# CPU.net
KiCad netlist of a schematic drawn in Altium Designer
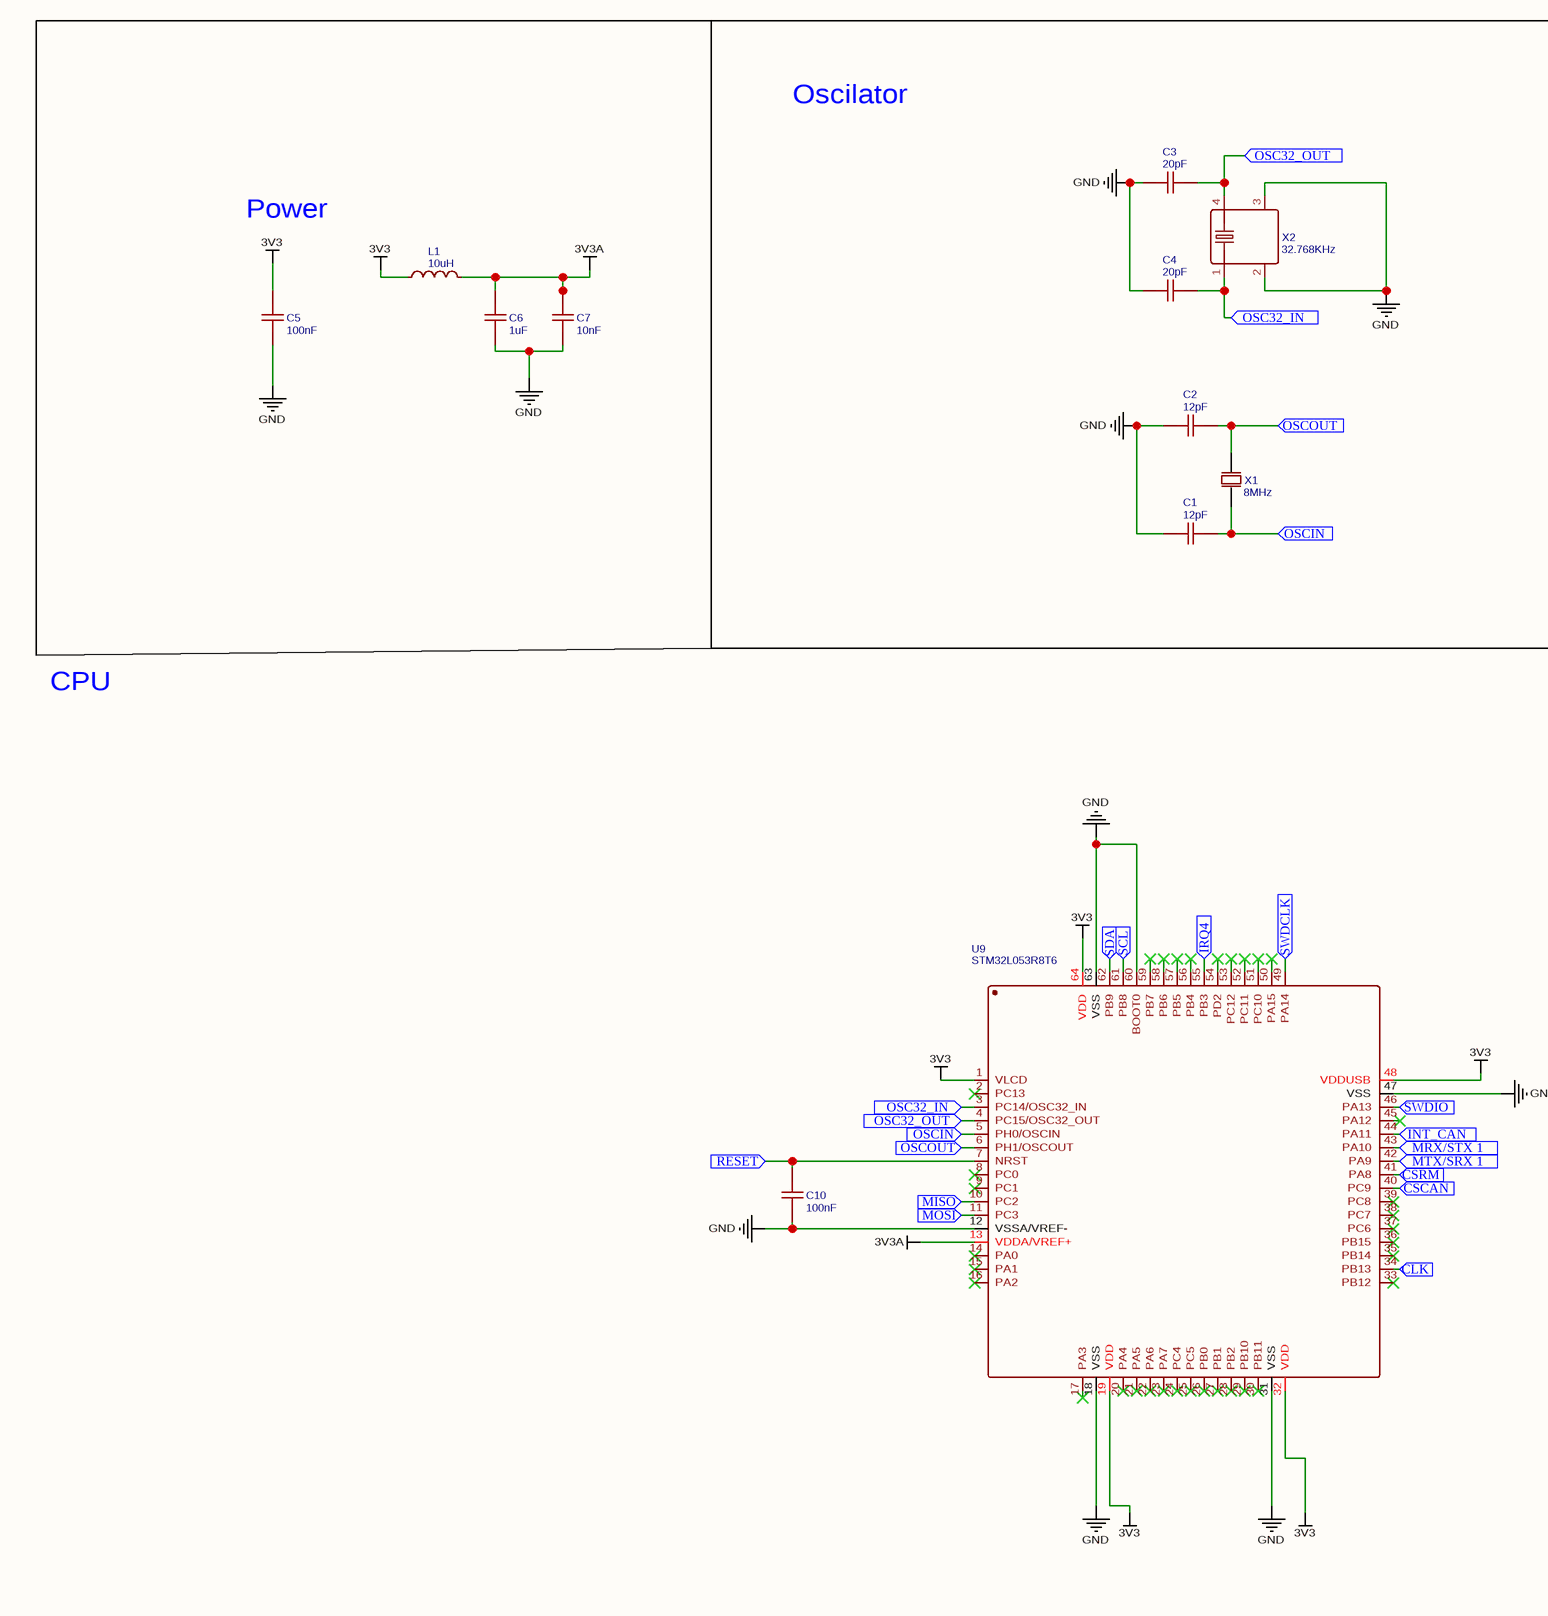
[diagram p0: CPU.schdoc, left]
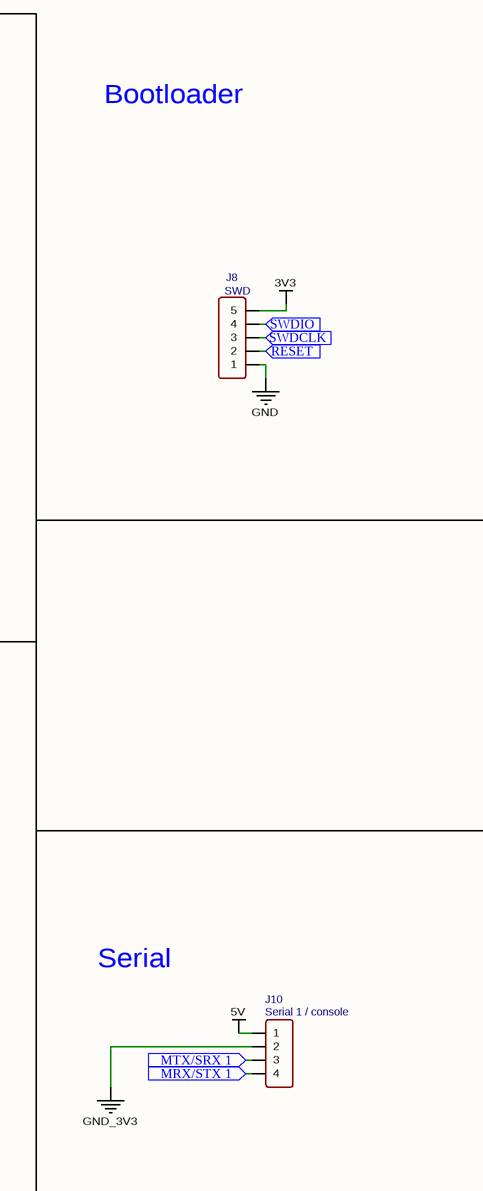
[diagram p1: CPU.schdoc, right]

(export (version "E")
  (design (tool "Eeschema 10.0.6"))
  (components
    (comp (ref "C1")
      (value "12pF")
      (fields
        (field (name "BOM_SUPPLIER PART") "C170110")
        (field (name "BOM_MANUFACTURER PART") "CL21C120JBANNNC")
        (field (name "CONTRIBUTOR") "LCEDA_Lib")
      )
      (libsource (lib "altium-import") (part "root_0_12pF_"))
    )
    (comp (ref "C2")
      (value "12pF")
      (fields
        (field (name "BOM_SUPPLIER PART") "C170110")
        (field (name "BOM_MANUFACTURER PART") "CL21C120JBANNNC")
        (field (name "CONTRIBUTOR") "LCEDA_Lib")
      )
      (libsource (lib "altium-import") (part "root_0_12pF_"))
    )
    (comp (ref "C3")
      (value "20pF")
      (fields
        (field (name "BOM_SUPPLIER PART") "C105173")
        (field (name "BOM_MANUFACTURER PART") "CC0805JRNPO9BN200")
        (field (name "CONTRIBUTOR") "LCEDA_Lib")
      )
      (libsource (lib "altium-import") (part "root_0_20pF_"))
    )
    (comp (ref "C4")
      (value "20pF")
      (fields
        (field (name "BOM_SUPPLIER PART") "C105173")
        (field (name "BOM_MANUFACTURER PART") "CC0805JRNPO9BN200")
        (field (name "CONTRIBUTOR") "LCEDA_Lib")
      )
      (libsource (lib "altium-import") (part "root_0_20pF_"))
    )
    (comp (ref "C5")
      (value "100nF")
      (fields
        (field (name "BOM_SUPPLIER PART") "C49678")
        (field (name "BOM_MANUFACTURER PART") "CC0805KRX7R9BB104")
        (field (name "CONTRIBUTOR") "LCEDA_Lib")
      )
      (libsource (lib "altium-import") (part "root_1_100nF_"))
    )
    (comp (ref "C6")
      (value "1uF")
      (fields
        (field (name "BOM_SUPPLIER PART") "C77080")
        (field (name "BOM_MANUFACTURER PART") "GRM21BR71E105KA99L")
        (field (name "CONTRIBUTOR") "LCEDA_Lib")
      )
      (libsource (lib "altium-import") (part "root_1_1uF_"))
    )
    (comp (ref "C7")
      (value "10nF")
      (fields
        (field (name "BOM_SUPPLIER PART") "C2971995")
        (field (name "BOM_MANUFACTURER PART") "0805CG103J500NT")
        (field (name "CONTRIBUTOR") "LCEDA_Lib")
      )
      (libsource (lib "altium-import") (part "root_1_10nF_"))
    )
    (comp (ref "C10")
      (value "100nF")
      (fields
        (field (name "BOM_SUPPLIER PART") "C49678")
        (field (name "BOM_MANUFACTURER PART") "CC0805KRX7R9BB104")
        (field (name "CONTRIBUTOR") "LCEDA_Lib")
      )
      (libsource (lib "altium-import") (part "root_1_100nF_"))
    )
    (comp (ref "J8")
      (value "SWD")
      (fields (field (name "BOM_SUPPLIER PART") "C358687") (field (name "CONTRIBUTOR") "LCEDA_Lib"))
      (libsource (lib "altium-import") (part "root_2_SWD_"))
    )
    (comp (ref "J10")
      (value "Serial 1 / console")
      (fields (field (name "BOM_SUPPLIER PART") "C124378") (field (name "CONTRIBUTOR") "LCEDA_Lib"))
      (libsource (lib "altium-import") (part "root_0_Serial 1 / console_"))
    )
    (comp (ref "L1")
      (value "10uH")
      (fields
        (field (name "BOM_MANUFACTURER PART") "CMI321609X100KT")
        (field (name "BOM_SUPPLIER PART") "C1051")
      )
      (libsource (lib "altium-import") (part "root_0_10uH_"))
    )
    (comp (ref "U9")
      (value "STM32L053R8T6")
      (fields
        (field (name "BOM_MANUFACTURER PART") "STM32L053R6T6")
        (field (name "BOM_SUPPLIER PART") "C1339433")
      )
      (libsource (lib "altium-import") (part "root_0_STM32L053R8T6_"))
    )
    (comp (ref "X1")
      (value "8MHz")
      (fields
        (field (name "BOM_MANUFACTURER PART") "X50328MSB2GI")
        (field (name "BOM_SUPPLIER PART") "C115962")
      )
      (libsource (lib "altium-import") (part "root_1_8MHz_"))
    )
    (comp (ref "X2")
      (value "32.768KHz")
      (fields
        (field (name "BOM_MANUFACTURER PART") "MC-306 32.768kHz 6.0pF 20ppm")
        (field (name "BOM_SUPPLIER PART") "C83979")
        (field (name "CONTRIBUTOR") "LCSC")
      )
      (libsource (lib "altium-import") (part "root_0_32.768KHz_"))
    )
  )
  (nets
    (net (code "1") (name "/CLK") (class "Default")
      (node (ref "U9") (pin "34") (pinfunction "PB13_34") (pintype "passive"))
    )
    (net (code "2") (name "/CSCAN") (class "Default")
      (node (ref "U9") (pin "40") (pinfunction "PC9_40") (pintype "passive"))
    )
    (net (code "3") (name "/CSRM") (class "Default")
      (node (ref "U9") (pin "41") (pinfunction "PA8_41") (pintype "passive"))
    )
    (net (code "4") (name "/INT_CAN") (class "Default")
      (node (ref "U9") (pin "44") (pinfunction "PA11_44") (pintype "passive"))
    )
    (net (code "5") (name "/IRQ4") (class "Default")
      (node (ref "U9") (pin "55") (pinfunction "PB3_55") (pintype "passive"))
    )
    (net (code "6") (name "/MISO") (class "Default")
      (node (ref "U9") (pin "10") (pinfunction "PC2_10") (pintype "passive"))
    )
    (net (code "7") (name "/MOSI") (class "Default")
      (node (ref "U9") (pin "11") (pinfunction "PC3_11") (pintype "passive"))
    )
    (net (code "8") (name "/MRX{slash}STX 1") (class "Default")
      (node (ref "J10") (pin "4") (pinfunction "4_4") (pintype "passive"))
      (node (ref "U9") (pin "43") (pinfunction "PA10_43") (pintype "passive"))
    )
    (net (code "9") (name "/MTX{slash}SRX 1") (class "Default")
      (node (ref "J10") (pin "3") (pinfunction "3_3") (pintype "passive"))
      (node (ref "U9") (pin "42") (pinfunction "PA9_42") (pintype "passive"))
    )
    (net (code "10") (name "/OSC32_IN") (class "Default")
      (node (ref "C4") (pin "2") (pinfunction "2_2") (pintype "passive"))
      (node (ref "U9") (pin "3") (pinfunction "PC14/OSC32_IN_3") (pintype "passive"))
      (node (ref "X2") (pin "1") (pinfunction "1_1") (pintype "passive"))
    )
    (net (code "11") (name "/OSC32_OUT") (class "Default")
      (node (ref "C3") (pin "2") (pinfunction "2_2") (pintype "passive"))
      (node (ref "U9") (pin "4") (pinfunction "PC15/OSC32_OUT_4") (pintype "passive"))
      (node (ref "X2") (pin "4") (pinfunction "4_4") (pintype "passive"))
    )
    (net (code "12") (name "/OSCIN") (class "Default")
      (node (ref "C1") (pin "2") (pinfunction "2_2") (pintype "passive"))
      (node (ref "U9") (pin "5") (pinfunction "PH0/OSCIN_5") (pintype "passive"))
      (node (ref "X1") (pin "1") (pinfunction "OSC1_1") (pintype "passive"))
    )
    (net (code "13") (name "/OSCOUT") (class "Default")
      (node (ref "C2") (pin "2") (pinfunction "2_2") (pintype "passive"))
      (node (ref "U9") (pin "6") (pinfunction "PH1/OSCOUT_6") (pintype "passive"))
      (node (ref "X1") (pin "2") (pinfunction "OSC2_2") (pintype "passive"))
    )
    (net (code "14") (name "/RESET") (class "Default")
      (node (ref "C10") (pin "2") (pinfunction "2_2") (pintype "passive"))
      (node (ref "J8") (pin "2") (pinfunction "2_2") (pintype "passive"))
      (node (ref "U9") (pin "7") (pinfunction "NRST_7") (pintype "passive"))
    )
    (net (code "15") (name "/SCL") (class "Default")
      (node (ref "U9") (pin "61") (pinfunction "PB8_61") (pintype "passive"))
    )
    (net (code "16") (name "/SDA") (class "Default")
      (node (ref "U9") (pin "62") (pinfunction "PB9_62") (pintype "passive"))
    )
    (net (code "17") (name "/SWDCLK") (class "Default")
      (node (ref "J8") (pin "3") (pinfunction "3_3") (pintype "passive"))
      (node (ref "U9") (pin "49") (pinfunction "PA14_49") (pintype "passive"))
    )
    (net (code "18") (name "/SWDIO") (class "Default")
      (node (ref "J8") (pin "4") (pinfunction "4_4") (pintype "passive"))
      (node (ref "U9") (pin "46") (pinfunction "PA13_46") (pintype "passive"))
    )
    (net (code "19") (name "3V3") (class "Default")
      (node (ref "C5") (pin "2") (pinfunction "2_2") (pintype "passive"))
      (node (ref "J8") (pin "5") (pinfunction "5_5") (pintype "passive"))
      (node (ref "L1") (pin "1") (pinfunction "1_1") (pintype "passive"))
      (node (ref "U9") (pin "1") (pinfunction "VLCD_1") (pintype "passive"))
      (node (ref "U9") (pin "19") (pinfunction "VDD_19") (pintype "passive"))
      (node (ref "U9") (pin "32") (pinfunction "VDD_32") (pintype "passive"))
      (node (ref "U9") (pin "48") (pinfunction "VDDUSB_48") (pintype "passive"))
      (node (ref "U9") (pin "64") (pinfunction "VDD_64") (pintype "passive"))
    )
    (net (code "20") (name "3V3A") (class "Default")
      (node (ref "C6") (pin "2") (pinfunction "2_2") (pintype "passive"))
      (node (ref "C7") (pin "2") (pinfunction "2_2") (pintype "passive"))
      (node (ref "L1") (pin "2") (pinfunction "2_2") (pintype "passive"))
      (node (ref "U9") (pin "13") (pinfunction "VDDA/VREF+_13") (pintype "passive"))
    )
    (net (code "21") (name "5V") (class "Default")
      (node (ref "J10") (pin "1") (pinfunction "1_1") (pintype "passive"))
    )
    (net (code "22") (name "GND") (class "Default")
      (node (ref "C1") (pin "1") (pinfunction "1_1") (pintype "passive"))
      (node (ref "C10") (pin "1") (pinfunction "1_1") (pintype "passive"))
      (node (ref "C2") (pin "1") (pinfunction "1_1") (pintype "passive"))
      (node (ref "C3") (pin "1") (pinfunction "1_1") (pintype "passive"))
      (node (ref "C4") (pin "1") (pinfunction "1_1") (pintype "passive"))
      (node (ref "C5") (pin "1") (pinfunction "1_1") (pintype "passive"))
      (node (ref "C6") (pin "1") (pinfunction "1_1") (pintype "passive"))
      (node (ref "C7") (pin "1") (pinfunction "1_1") (pintype "passive"))
      (node (ref "J8") (pin "1") (pinfunction "1_1") (pintype "passive"))
      (node (ref "U9") (pin "12") (pinfunction "VSSA/VREF-_12") (pintype "passive"))
      (node (ref "U9") (pin "18") (pinfunction "VSS_18") (pintype "passive"))
      (node (ref "U9") (pin "31") (pinfunction "VSS_31") (pintype "passive"))
      (node (ref "U9") (pin "47") (pinfunction "VSS_47") (pintype "passive"))
      (node (ref "U9") (pin "60") (pinfunction "BOOT0_60") (pintype "passive"))
      (node (ref "U9") (pin "63") (pinfunction "VSS_63") (pintype "passive"))
      (node (ref "X2") (pin "2") (pinfunction "2_2") (pintype "passive"))
      (node (ref "X2") (pin "3") (pinfunction "3_3") (pintype "passive"))
    )
    (net (code "23") (name "GND_3V3") (class "Default")
      (node (ref "J10") (pin "2") (pinfunction "2_2") (pintype "passive"))
    )
    (net (code "24") (name "unconnected-(U9-PA0-Pad14)") (class "Default")
      (node (ref "U9") (pin "14") (pinfunction "PA0_14") (pintype "passive+no_connect"))
    )
    (net (code "25") (name "unconnected-(U9-PA1-Pad15)") (class "Default")
      (node (ref "U9") (pin "15") (pinfunction "PA1_15") (pintype "passive+no_connect"))
    )
    (net (code "26") (name "unconnected-(U9-PA2-Pad16)") (class "Default")
      (node (ref "U9") (pin "16") (pinfunction "PA2_16") (pintype "passive+no_connect"))
    )
    (net (code "27") (name "unconnected-(U9-PA3-Pad17)") (class "Default")
      (node (ref "U9") (pin "17") (pinfunction "PA3_17") (pintype "passive+no_connect"))
    )
    (net (code "28") (name "unconnected-(U9-PA4-Pad20)") (class "Default")
      (node (ref "U9") (pin "20") (pinfunction "PA4_20") (pintype "passive+no_connect"))
    )
    (net (code "29") (name "unconnected-(U9-PA5-Pad21)") (class "Default")
      (node (ref "U9") (pin "21") (pinfunction "PA5_21") (pintype "passive+no_connect"))
    )
    (net (code "30") (name "unconnected-(U9-PA6-Pad22)") (class "Default")
      (node (ref "U9") (pin "22") (pinfunction "PA6_22") (pintype "passive+no_connect"))
    )
    (net (code "31") (name "unconnected-(U9-PA7-Pad23)") (class "Default")
      (node (ref "U9") (pin "23") (pinfunction "PA7_23") (pintype "passive+no_connect"))
    )
    (net (code "32") (name "unconnected-(U9-PA12-Pad45)") (class "Default")
      (node (ref "U9") (pin "45") (pinfunction "PA12_45") (pintype "passive+no_connect"))
    )
    (net (code "33") (name "unconnected-(U9-PA15-Pad50)") (class "Default")
      (node (ref "U9") (pin "50") (pinfunction "PA15_50") (pintype "passive+no_connect"))
    )
    (net (code "34") (name "unconnected-(U9-PB0-Pad26)") (class "Default")
      (node (ref "U9") (pin "26") (pinfunction "PB0_26") (pintype "passive+no_connect"))
    )
    (net (code "35") (name "unconnected-(U9-PB1-Pad27)") (class "Default")
      (node (ref "U9") (pin "27") (pinfunction "PB1_27") (pintype "passive+no_connect"))
    )
    (net (code "36") (name "unconnected-(U9-PB2-Pad28)") (class "Default")
      (node (ref "U9") (pin "28") (pinfunction "PB2_28") (pintype "passive+no_connect"))
    )
    (net (code "37") (name "unconnected-(U9-PB4-Pad56)") (class "Default")
      (node (ref "U9") (pin "56") (pinfunction "PB4_56") (pintype "passive+no_connect"))
    )
    (net (code "38") (name "unconnected-(U9-PB5-Pad57)") (class "Default")
      (node (ref "U9") (pin "57") (pinfunction "PB5_57") (pintype "passive+no_connect"))
    )
    (net (code "39") (name "unconnected-(U9-PB6-Pad58)") (class "Default")
      (node (ref "U9") (pin "58") (pinfunction "PB6_58") (pintype "passive+no_connect"))
    )
    (net (code "40") (name "unconnected-(U9-PB7-Pad59)") (class "Default")
      (node (ref "U9") (pin "59") (pinfunction "PB7_59") (pintype "passive+no_connect"))
    )
    (net (code "41") (name "unconnected-(U9-PB10-Pad29)") (class "Default")
      (node (ref "U9") (pin "29") (pinfunction "PB10_29") (pintype "passive+no_connect"))
    )
    (net (code "42") (name "unconnected-(U9-PB11-Pad30)") (class "Default")
      (node (ref "U9") (pin "30") (pinfunction "PB11_30") (pintype "passive+no_connect"))
    )
    (net (code "43") (name "unconnected-(U9-PB12-Pad33)") (class "Default")
      (node (ref "U9") (pin "33") (pinfunction "PB12_33") (pintype "passive+no_connect"))
    )
    (net (code "44") (name "unconnected-(U9-PB14-Pad35)") (class "Default")
      (node (ref "U9") (pin "35") (pinfunction "PB14_35") (pintype "passive+no_connect"))
    )
    (net (code "45") (name "unconnected-(U9-PB15-Pad36)") (class "Default")
      (node (ref "U9") (pin "36") (pinfunction "PB15_36") (pintype "passive+no_connect"))
    )
    (net (code "46") (name "unconnected-(U9-PC0-Pad8)") (class "Default")
      (node (ref "U9") (pin "8") (pinfunction "PC0_8") (pintype "passive+no_connect"))
    )
    (net (code "47") (name "unconnected-(U9-PC1-Pad9)") (class "Default")
      (node (ref "U9") (pin "9") (pinfunction "PC1_9") (pintype "passive+no_connect"))
    )
    (net (code "48") (name "unconnected-(U9-PC4-Pad24)") (class "Default")
      (node (ref "U9") (pin "24") (pinfunction "PC4_24") (pintype "passive+no_connect"))
    )
    (net (code "49") (name "unconnected-(U9-PC5-Pad25)") (class "Default")
      (node (ref "U9") (pin "25") (pinfunction "PC5_25") (pintype "passive+no_connect"))
    )
    (net (code "50") (name "unconnected-(U9-PC6-Pad37)") (class "Default")
      (node (ref "U9") (pin "37") (pinfunction "PC6_37") (pintype "passive+no_connect"))
    )
    (net (code "51") (name "unconnected-(U9-PC7-Pad38)") (class "Default")
      (node (ref "U9") (pin "38") (pinfunction "PC7_38") (pintype "passive+no_connect"))
    )
    (net (code "52") (name "unconnected-(U9-PC8-Pad39)") (class "Default")
      (node (ref "U9") (pin "39") (pinfunction "PC8_39") (pintype "passive+no_connect"))
    )
    (net (code "53") (name "unconnected-(U9-PC10-Pad51)") (class "Default")
      (node (ref "U9") (pin "51") (pinfunction "PC10_51") (pintype "passive+no_connect"))
    )
    (net (code "54") (name "unconnected-(U9-PC11-Pad52)") (class "Default")
      (node (ref "U9") (pin "52") (pinfunction "PC11_52") (pintype "passive+no_connect"))
    )
    (net (code "55") (name "unconnected-(U9-PC12-Pad53)") (class "Default")
      (node (ref "U9") (pin "53") (pinfunction "PC12_53") (pintype "passive+no_connect"))
    )
    (net (code "56") (name "unconnected-(U9-PC13-Pad2)") (class "Default")
      (node (ref "U9") (pin "2") (pinfunction "PC13_2") (pintype "passive+no_connect"))
    )
    (net (code "57") (name "unconnected-(U9-PD2-Pad54)") (class "Default")
      (node (ref "U9") (pin "54") (pinfunction "PD2_54") (pintype "passive+no_connect"))
    )
  )
)
